# 1_MCU.net
KiCad netlist of a schematic drawn in Altium Designer
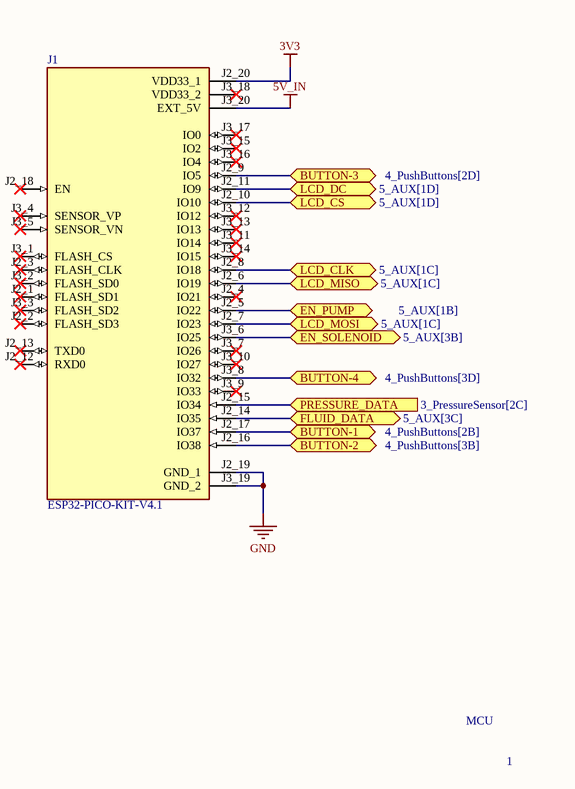
[diagram p0: 1_MCU.SchDoc]

(export (version "E")
  (design (tool "Eeschema 10.0.6"))
  (components
    (comp (ref "J1")
      (value "ESP32-PICO-KIT-V4.1")
      (footprint "XCVR_ESP32-PICO-KIT-V4.1")
      (description "WiFi Development Tools (802.11)")
      (fields (field (name "MF") "Espressif Systems"))
      (libsource (lib "McMaster University") (part "ESP32-PICO-KIT-V4.1"))
    )
  )
  (nets
    (net (code "1") (name "/BUTTON-1") (class "Default")
      (node (ref "J1") (pin "J2_17") (pinfunction "IO37_J2_17") (pintype "input"))
    )
    (net (code "2") (name "/BUTTON-2") (class "Default")
      (node (ref "J1") (pin "J2_16") (pinfunction "IO38_J2_16") (pintype "input"))
    )
    (net (code "3") (name "/BUTTON-3") (class "Default")
      (node (ref "J1") (pin "J2_9") (pinfunction "IO5_J2_9") (pintype "bidirectional"))
    )
    (net (code "4") (name "/BUTTON-4") (class "Default")
      (node (ref "J1") (pin "J3_8") (pinfunction "IO32_J3_8") (pintype "bidirectional"))
    )
    (net (code "5") (name "/EN_PUMP") (class "Default")
      (node (ref "J1") (pin "J2_5") (pinfunction "IO22_J2_5") (pintype "bidirectional"))
    )
    (net (code "6") (name "/EN_SOLENOID") (class "Default")
      (node (ref "J1") (pin "J3_6") (pinfunction "IO25_J3_6") (pintype "bidirectional"))
    )
    (net (code "7") (name "/FLUID_DATA") (class "Default")
      (node (ref "J1") (pin "J2_14") (pinfunction "IO35_J2_14") (pintype "input"))
    )
    (net (code "8") (name "/LCD_CLK") (class "Default")
      (node (ref "J1") (pin "J2_8") (pinfunction "IO18_J2_8") (pintype "bidirectional"))
    )
    (net (code "9") (name "/LCD_CS") (class "Default")
      (node (ref "J1") (pin "J2_10") (pinfunction "IO10_J2_10") (pintype "bidirectional"))
    )
    (net (code "10") (name "/LCD_DC") (class "Default")
      (node (ref "J1") (pin "J2_11") (pinfunction "IO9_J2_11") (pintype "bidirectional"))
    )
    (net (code "11") (name "/LCD_MISO") (class "Default")
      (node (ref "J1") (pin "J2_6") (pinfunction "IO19_J2_6") (pintype "bidirectional"))
    )
    (net (code "12") (name "/LCD_MOSI") (class "Default")
      (node (ref "J1") (pin "J2_7") (pinfunction "IO23_J2_7") (pintype "bidirectional"))
    )
    (net (code "13") (name "/PRESSURE_DATA") (class "Default")
      (node (ref "J1") (pin "J2_15") (pinfunction "IO34_J2_15") (pintype "input"))
    )
    (net (code "14") (name "3V3") (class "Default")
      (node (ref "J1") (pin "J2_20") (pinfunction "VDD33_1_J2_20") (pintype "power_in"))
    )
    (net (code "15") (name "5V_IN") (class "Default")
      (node (ref "J1") (pin "J3_20") (pinfunction "EXT_5V_J3_20") (pintype "power_in"))
    )
    (net (code "16") (name "GND") (class "Default")
      (node (ref "J1") (pin "J2_19") (pinfunction "GND_1_J2_19") (pintype "power_in"))
      (node (ref "J1") (pin "J3_19") (pinfunction "GND_2_J3_19") (pintype "power_in"))
    )
    (net (code "17") (name "unconnected-(J1-EN-PadJ2_18)") (class "Default")
      (node (ref "J1") (pin "J2_18") (pinfunction "EN_J2_18") (pintype "input+no_connect"))
    )
    (net (code "18") (name "unconnected-(J1-FLASH_CLK-PadJ2_3)") (class "Default")
      (node (ref "J1") (pin "J2_3") (pinfunction "FLASH_CLK_J2_3") (pintype "bidirectional+no_connect"))
    )
    (net (code "19") (name "unconnected-(J1-FLASH_CS-PadJ3_1)") (class "Default")
      (node (ref "J1") (pin "J3_1") (pinfunction "FLASH_CS_J3_1") (pintype "bidirectional+no_connect"))
    )
    (net (code "20") (name "unconnected-(J1-FLASH_SD0-PadJ3_2)") (class "Default")
      (node (ref "J1") (pin "J3_2") (pinfunction "FLASH_SD0_J3_2") (pintype "bidirectional+no_connect"))
    )
    (net (code "21") (name "unconnected-(J1-FLASH_SD1-PadJ2_1)") (class "Default")
      (node (ref "J1") (pin "J2_1") (pinfunction "FLASH_SD1_J2_1") (pintype "bidirectional+no_connect"))
    )
    (net (code "22") (name "unconnected-(J1-FLASH_SD2-PadJ3_3)") (class "Default")
      (node (ref "J1") (pin "J3_3") (pinfunction "FLASH_SD2_J3_3") (pintype "bidirectional+no_connect"))
    )
    (net (code "23") (name "unconnected-(J1-FLASH_SD3-PadJ2_2)") (class "Default")
      (node (ref "J1") (pin "J2_2") (pinfunction "FLASH_SD3_J2_2") (pintype "bidirectional+no_connect"))
    )
    (net (code "24") (name "unconnected-(J1-IO0-PadJ3_17)") (class "Default")
      (node (ref "J1") (pin "J3_17") (pinfunction "IO0_J3_17") (pintype "bidirectional+no_connect"))
    )
    (net (code "25") (name "unconnected-(J1-IO2-PadJ3_15)") (class "Default")
      (node (ref "J1") (pin "J3_15") (pinfunction "IO2_J3_15") (pintype "bidirectional+no_connect"))
    )
    (net (code "26") (name "unconnected-(J1-IO4-PadJ3_16)") (class "Default")
      (node (ref "J1") (pin "J3_16") (pinfunction "IO4_J3_16") (pintype "bidirectional+no_connect"))
    )
    (net (code "27") (name "unconnected-(J1-IO12-PadJ3_12)") (class "Default")
      (node (ref "J1") (pin "J3_12") (pinfunction "IO12_J3_12") (pintype "bidirectional+no_connect"))
    )
    (net (code "28") (name "unconnected-(J1-IO13-PadJ3_13)") (class "Default")
      (node (ref "J1") (pin "J3_13") (pinfunction "IO13_J3_13") (pintype "bidirectional+no_connect"))
    )
    (net (code "29") (name "unconnected-(J1-IO14-PadJ3_11)") (class "Default")
      (node (ref "J1") (pin "J3_11") (pinfunction "IO14_J3_11") (pintype "bidirectional+no_connect"))
    )
    (net (code "30") (name "unconnected-(J1-IO15-PadJ3_14)") (class "Default")
      (node (ref "J1") (pin "J3_14") (pinfunction "IO15_J3_14") (pintype "bidirectional+no_connect"))
    )
    (net (code "31") (name "unconnected-(J1-IO21-PadJ2_4)") (class "Default")
      (node (ref "J1") (pin "J2_4") (pinfunction "IO21_J2_4") (pintype "bidirectional+no_connect"))
    )
    (net (code "32") (name "unconnected-(J1-IO26-PadJ3_7)") (class "Default")
      (node (ref "J1") (pin "J3_7") (pinfunction "IO26_J3_7") (pintype "bidirectional+no_connect"))
    )
    (net (code "33") (name "unconnected-(J1-IO27-PadJ3_10)") (class "Default")
      (node (ref "J1") (pin "J3_10") (pinfunction "IO27_J3_10") (pintype "bidirectional+no_connect"))
    )
    (net (code "34") (name "unconnected-(J1-IO33-PadJ3_9)") (class "Default")
      (node (ref "J1") (pin "J3_9") (pinfunction "IO33_J3_9") (pintype "bidirectional+no_connect"))
    )
    (net (code "35") (name "unconnected-(J1-RXD0-PadJ2_12)") (class "Default")
      (node (ref "J1") (pin "J2_12") (pinfunction "RXD0_J2_12") (pintype "bidirectional+no_connect"))
    )
    (net (code "36") (name "unconnected-(J1-SENSOR_VN-PadJ3_5)") (class "Default")
      (node (ref "J1") (pin "J3_5") (pinfunction "SENSOR_VN_J3_5") (pintype "input+no_connect"))
    )
    (net (code "37") (name "unconnected-(J1-SENSOR_VP-PadJ3_4)") (class "Default")
      (node (ref "J1") (pin "J3_4") (pinfunction "SENSOR_VP_J3_4") (pintype "input+no_connect"))
    )
    (net (code "38") (name "unconnected-(J1-TXD0-PadJ2_13)") (class "Default")
      (node (ref "J1") (pin "J2_13") (pinfunction "TXD0_J2_13") (pintype "bidirectional+no_connect"))
    )
    (net (code "39") (name "unconnected-(J1-VDD33_2-PadJ3_18)") (class "Default")
      (node (ref "J1") (pin "J3_18") (pinfunction "VDD33_2_J3_18") (pintype "power_in+no_connect"))
    )
  )
)
